# Buck_converter.net
KiCad netlist of a schematic drawn in Altium Designer
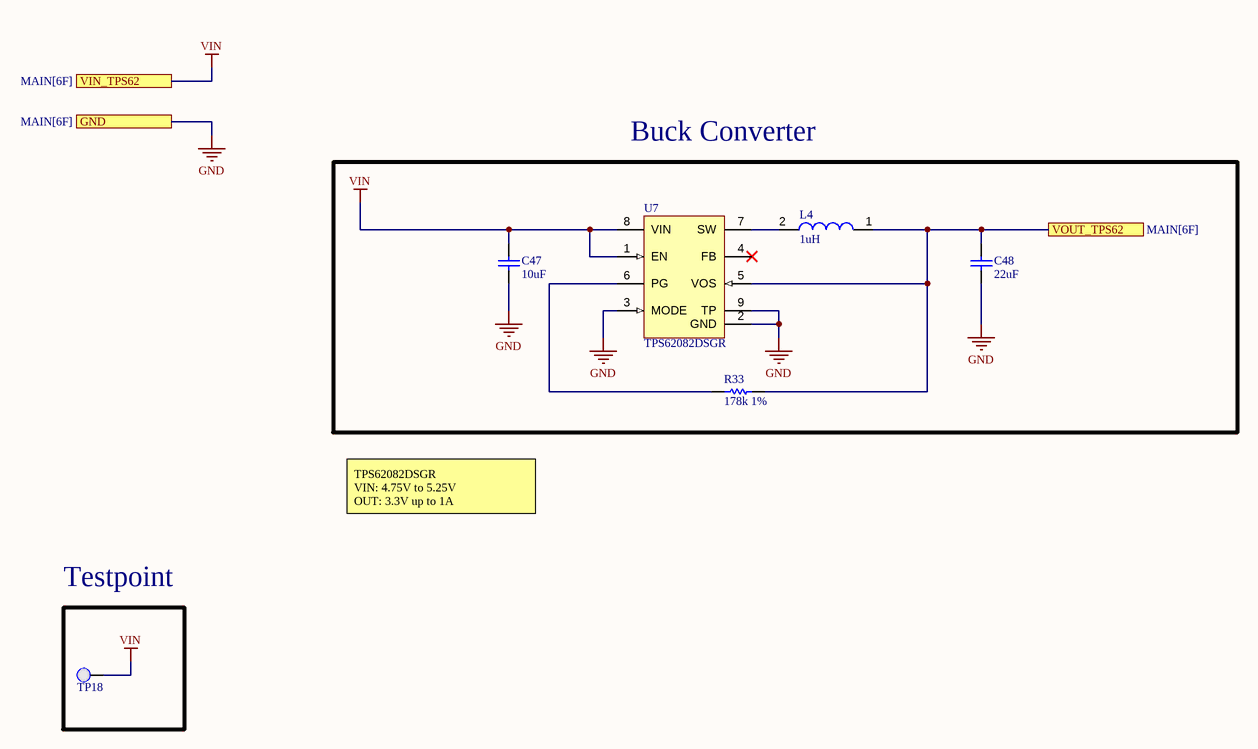
[diagram p0: Buck converter.SchDoc]

(export (version "E")
  (design (tool "Eeschema 10.0.6"))
  (components
    (comp (ref "C47")
      (value "10uF")
      (footprint "CAPC2012X127N")
      (description "Boost Cin, Buck Cin-Cap Ceramic 10uF 16V X7R 20% SMD 0805 125°C Blister T/R")
      (fields (field (name "TOLERANCE") "20%") (field (name "MANUFACTURER") "Murata"))
      (libsource (lib "Schlib1") (part "CMP-06035-062410-1"))
    )
    (comp (ref "C48")
      (value "22uF")
      (footprint "CAPC2012X127N")
      (description "Buck Cout, Multilayer Ceramic Capacitors 0805 25V X5R 226 20% 7'REEL PLASTIC")
      (fields
        (field (name "MANUFACTURER") "Murata")
        (field (name "MANUFACTURER PART NUMBER") "GRM188R60J226MEA0D")
      )
      (libsource (lib "Schlib1") (part "GRM188R60J226MEA0D"))
    )
    (comp (ref "L4")
      (value "1uH")
      (footprint "744316100")
      (fields
        (field (name "MANUFACTURER") "Wurth Electronics")
        (field (name "MANUFACTURER PART NUMBER") "744316100")
        (field (name "TOLERANCE") "20%")
      )
      (libsource (lib "Schlib1") (part "744316100"))
    )
    (comp (ref "R33")
      (value "178k 1%")
      (footprint "RESC1005X40X25NL05T05")
      (description "Buck Rpg, Res Thick Film 0402 178K Ohm 1% 0.063W ±100ppm/°C Molded SMD Paper T/R")
      (fields (field (name "PART NUMBER") "ERJ-2RKF1783X") (field (name "MANUFACTURER") "Panasonic"))
      (libsource (lib "Schlib1") (part "CMP-2002-00733-1"))
    )
    (comp (ref "TP18")
      (value "0.1\" Pad")
      (footprint "PCBComponent")
      (libsource (lib "Components - 12.02.20 - 18.05") (part "0.1{dblquote} Pad-A.4"))
    )
    (comp (ref "U7")
      (value "TPS62082DSGR")
      (footprint "DSG0008A_V")
      (fields (field (name "MANUFACTURER") "Texas Instruments"))
      (libsource (lib "Altium Content Vault") (part "TI-TPS62082DSG8-1600X900TP"))
    )
  )
  (nets
    (net (code "1") (name "/VOUT_TPS62") (class "Default")
      (node (ref "C48") (pin "2") (pinfunction "2_2") (pintype "passive"))
      (node (ref "L4") (pin "1") (pinfunction "1_1") (pintype "passive"))
      (node (ref "R33") (pin "2") (pinfunction "2_2") (pintype "passive"))
      (node (ref "U7") (pin "5") (pinfunction "VOS_5") (pintype "input"))
    )
    (net (code "2") (name "GND") (class "Default")
      (node (ref "C47") (pin "1") (pinfunction "1_1") (pintype "passive"))
      (node (ref "C48") (pin "1") (pinfunction "1_1") (pintype "passive"))
      (node (ref "U7") (pin "2") (pinfunction "GND_2") (pintype "power_in"))
      (node (ref "U7") (pin "3") (pinfunction "MODE_3") (pintype "input"))
      (node (ref "U7") (pin "9") (pinfunction "TP_9") (pintype "power_in"))
    )
    (net (code "3") (name "Net-(U7-PG)") (class "Default")
      (node (ref "R33") (pin "1") (pinfunction "1_1") (pintype "passive"))
      (node (ref "U7") (pin "6") (pinfunction "PG_6") (pintype "tri_state"))
    )
    (net (code "4") (name "Net-(U7-SW)") (class "Default")
      (node (ref "L4") (pin "2") (pinfunction "2_2") (pintype "passive"))
      (node (ref "U7") (pin "7") (pinfunction "SW_7") (pintype "power_in"))
    )
    (net (code "5") (name "VIN") (class "Default")
      (node (ref "C47") (pin "2") (pinfunction "2_2") (pintype "passive"))
      (node (ref "TP18") (pin "1") (pinfunction "PAD_1") (pintype "passive"))
      (node (ref "U7") (pin "1") (pinfunction "EN_1") (pintype "input"))
      (node (ref "U7") (pin "8") (pinfunction "VIN_8") (pintype "power_in"))
    )
    (net (code "6") (name "unconnected-(U7-FB-Pad4)") (class "Default")
      (node (ref "U7") (pin "4") (pinfunction "FB_4") (pintype "passive+no_connect"))
    )
  )
)
